# Power_Supply.net
KiCad netlist of a schematic drawn in EAGLE
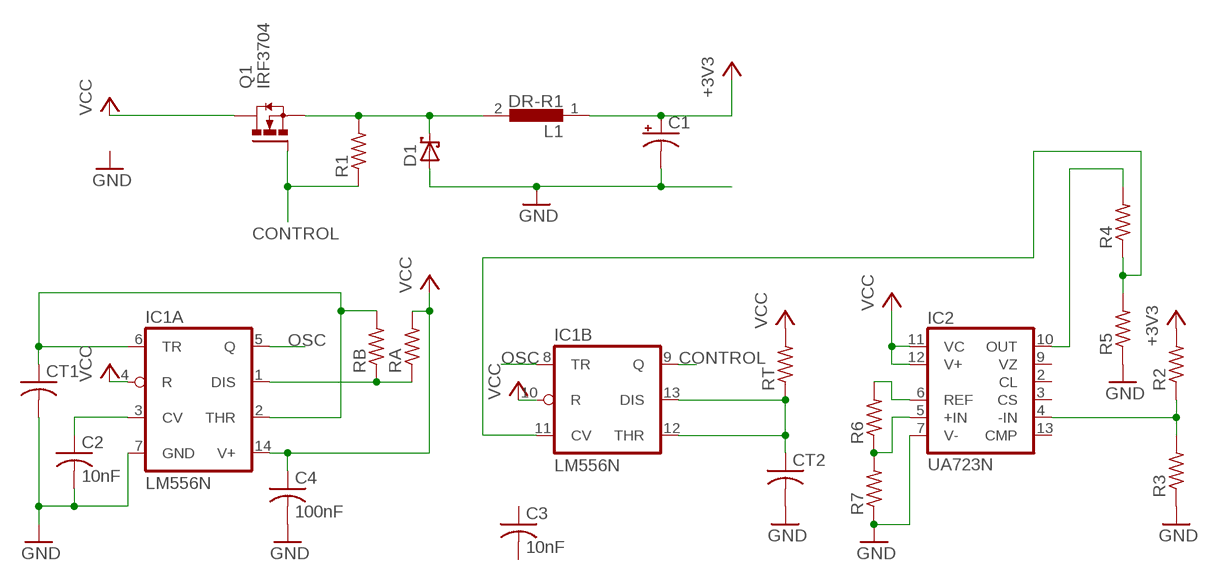
[diagram p0: schematic, sheet 1]

(export (version "E")
  (design (tool "Eeschema 10.0.6"))
  (components
    (comp (ref "C1")
      (value "CPOL-USE7.5-18")
      (footprint "eagle-import:E7,5-18")
      (libsource (lib "eagle-import") (part "CPOL-USE7.5-18"))
    )
    (comp (ref "C2")
      (value "10nF")
      (footprint "eagle-import:C050-025X075")
      (libsource (lib "eagle-import") (part "C-US050-025X075"))
    )
    (comp (ref "C3")
      (value "10nF")
      (footprint "eagle-import:C050-025X075")
      (libsource (lib "eagle-import") (part "C-US050-025X075"))
    )
    (comp (ref "C4")
      (value "100nF")
      (footprint "eagle-import:C050-025X075")
      (libsource (lib "eagle-import") (part "C-US050-025X075"))
    )
    (comp (ref "CT1")
      (value "C-US050-025X075")
      (footprint "eagle-import:C050-025X075")
      (libsource (lib "eagle-import") (part "C-US050-025X075"))
    )
    (comp (ref "CT2")
      (value "C-US050-025X075")
      (footprint "eagle-import:C050-025X075")
      (libsource (lib "eagle-import") (part "C-US050-025X075"))
    )
    (comp (ref "D1")
      (value "SCHOTTKY-DIODEC4111-15")
      (footprint "eagle-import:C4111-15")
      (libsource (lib "eagle-import") (part "SCHOTTKY-DIODEC4111-15"))
    )
    (comp (ref "IC1")
      (value "LM556N")
      (footprint "eagle-import:DIL14")
      (libsource (lib "eagle-import") (part "556NLM"))
    )
    (comp (ref "IC2")
      (value "UA723N")
      (footprint "eagle-import:DIL14")
      (libsource (lib "eagle-import") (part "723NUA"))
    )
    (comp (ref "L1")
      (value "DR-R1")
      (footprint "eagle-import:DR-R1")
      (libsource (lib "eagle-import") (part "DR-R1"))
    )
    (comp (ref "Q1")
      (value "IRF3704")
      (footprint "eagle-import:TO220AH")
      (libsource (lib "eagle-import") (part "IRF3704"))
    )
    (comp (ref "R1")
      (value "R-US_0207/10")
      (footprint "eagle-import:0207_10")
      (libsource (lib "eagle-import") (part "R-US_0207/10"))
    )
    (comp (ref "R2")
      (value "R-US_0207/10")
      (footprint "eagle-import:0207_10")
      (libsource (lib "eagle-import") (part "R-US_0207/10"))
    )
    (comp (ref "R3")
      (value "R-US_0207/10")
      (footprint "eagle-import:0207_10")
      (libsource (lib "eagle-import") (part "R-US_0207/10"))
    )
    (comp (ref "R4")
      (value "R-US_0207/10")
      (footprint "eagle-import:0207_10")
      (libsource (lib "eagle-import") (part "R-US_0207/10"))
    )
    (comp (ref "R5")
      (value "R-US_0207/10")
      (footprint "eagle-import:0207_10")
      (libsource (lib "eagle-import") (part "R-US_0207/10"))
    )
    (comp (ref "R6")
      (value "R-US_0207/10")
      (footprint "eagle-import:0207_10")
      (libsource (lib "eagle-import") (part "R-US_0207/10"))
    )
    (comp (ref "R7")
      (value "R-US_0207/10")
      (footprint "eagle-import:0207_10")
      (libsource (lib "eagle-import") (part "R-US_0207/10"))
    )
    (comp (ref "RA")
      (value "R-US_0207/10")
      (footprint "eagle-import:0207_10")
      (libsource (lib "eagle-import") (part "R-US_0207/10"))
    )
    (comp (ref "RB")
      (value "R-US_0207/10")
      (footprint "eagle-import:0207_10")
      (libsource (lib "eagle-import") (part "R-US_0207/10"))
    )
    (comp (ref "RT")
      (value "R-US_0207/10")
      (footprint "eagle-import:0207_10")
      (libsource (lib "eagle-import") (part "R-US_0207/10"))
    )
  )
  (nets
    (net (code "1") (name "+3V3") (class "Default")
      (node (ref "C1") (pin "+") (pinfunction "+_+") (pintype "passive"))
      (node (ref "L1") (pin "1") (pinfunction "1_1") (pintype "passive"))
      (node (ref "R2") (pin "2") (pinfunction "2_2") (pintype "passive"))
    )
    (net (code "2") (name "/CONTROL") (class "Default")
      (node (ref "IC1") (pin "9") (pinfunction "Q_9") (pintype "output"))
      (node (ref "Q1") (pin "B") (pinfunction "G_B") (pintype "passive"))
      (node (ref "R1") (pin "1") (pinfunction "1_1") (pintype "passive"))
    )
    (net (code "3") (name "/OSC") (class "Default")
      (node (ref "IC1") (pin "5") (pinfunction "Q_5") (pintype "output"))
      (node (ref "IC1") (pin "8") (pinfunction "TR_8") (pintype "input"))
    )
    (net (code "4") (name "GND") (class "Default")
      (node (ref "C1") (pin "-") (pinfunction "-_-") (pintype "passive"))
      (node (ref "C2") (pin "2") (pinfunction "2_2") (pintype "passive"))
      (node (ref "C4") (pin "2") (pinfunction "2_2") (pintype "passive"))
      (node (ref "CT1") (pin "2") (pinfunction "2_2") (pintype "passive"))
      (node (ref "CT2") (pin "2") (pinfunction "2_2") (pintype "passive"))
      (node (ref "D1") (pin "A") (pinfunction "A_A") (pintype "passive"))
      (node (ref "IC1") (pin "7") (pinfunction "GND_7") (pintype "power_in"))
      (node (ref "IC2") (pin "7") (pinfunction "V-_7") (pintype "input"))
      (node (ref "R3") (pin "1") (pinfunction "1_1") (pintype "passive"))
      (node (ref "R5") (pin "1") (pinfunction "1_1") (pintype "passive"))
      (node (ref "R7") (pin "1") (pinfunction "1_1") (pintype "passive"))
    )
    (net (code "5") (name "Net-(IC1A-CV)") (class "Default")
      (node (ref "C2") (pin "1") (pinfunction "1_1") (pintype "passive"))
      (node (ref "IC1") (pin "3") (pinfunction "CV_3") (pintype "input"))
    )
    (net (code "6") (name "Net-(IC1A-DIS)") (class "Default")
      (node (ref "IC1") (pin "1") (pinfunction "DIS_1") (pintype "input"))
      (node (ref "RA") (pin "1") (pinfunction "1_1") (pintype "passive"))
      (node (ref "RB") (pin "1") (pinfunction "1_1") (pintype "passive"))
    )
    (net (code "7") (name "Net-(IC1A-THR)") (class "Default")
      (node (ref "CT1") (pin "1") (pinfunction "1_1") (pintype "passive"))
      (node (ref "IC1") (pin "2") (pinfunction "THR_2") (pintype "input"))
      (node (ref "IC1") (pin "6") (pinfunction "TR_6") (pintype "input"))
      (node (ref "RB") (pin "2") (pinfunction "2_2") (pintype "passive"))
    )
    (net (code "8") (name "Net-(IC1B-CV)") (class "Default")
      (node (ref "IC1") (pin "11") (pinfunction "CV_11") (pintype "input"))
      (node (ref "R4") (pin "1") (pinfunction "1_1") (pintype "passive"))
      (node (ref "R5") (pin "2") (pinfunction "2_2") (pintype "passive"))
    )
    (net (code "9") (name "Net-(IC1B-DIS)") (class "Default")
      (node (ref "CT2") (pin "1") (pinfunction "1_1") (pintype "passive"))
      (node (ref "IC1") (pin "12") (pinfunction "THR_12") (pintype "input"))
      (node (ref "IC1") (pin "13") (pinfunction "DIS_13") (pintype "input"))
      (node (ref "RT") (pin "1") (pinfunction "1_1") (pintype "passive"))
    )
    (net (code "10") (name "Net-(IC2-+IN)") (class "Default")
      (node (ref "IC2") (pin "5") (pinfunction "+IN_5") (pintype "input"))
      (node (ref "R6") (pin "1") (pinfunction "1_1") (pintype "passive"))
      (node (ref "R7") (pin "2") (pinfunction "2_2") (pintype "passive"))
    )
    (net (code "11") (name "Net-(IC2--IN)") (class "Default")
      (node (ref "IC2") (pin "4") (pinfunction "-IN_4") (pintype "input"))
      (node (ref "R2") (pin "1") (pinfunction "1_1") (pintype "passive"))
      (node (ref "R3") (pin "2") (pinfunction "2_2") (pintype "passive"))
    )
    (net (code "12") (name "Net-(IC2-OUT)") (class "Default")
      (node (ref "IC2") (pin "10") (pinfunction "OUT_10") (pintype "output"))
      (node (ref "R4") (pin "2") (pinfunction "2_2") (pintype "passive"))
    )
    (net (code "13") (name "Net-(IC2-REF)") (class "Default")
      (node (ref "IC2") (pin "6") (pinfunction "REF_6") (pintype "output"))
      (node (ref "R6") (pin "2") (pinfunction "2_2") (pintype "passive"))
    )
    (net (code "14") (name "Net-(Q1-S)") (class "Default")
      (node (ref "D1") (pin "C") (pinfunction "C_C") (pintype "passive"))
      (node (ref "L1") (pin "2") (pinfunction "2_2") (pintype "passive"))
      (node (ref "Q1") (pin "E") (pinfunction "S_E") (pintype "passive"))
      (node (ref "R1") (pin "2") (pinfunction "2_2") (pintype "passive"))
    )
    (net (code "15") (name "VCC") (class "Default")
      (node (ref "C4") (pin "1") (pinfunction "1_1") (pintype "passive"))
      (node (ref "IC1") (pin "10") (pinfunction "R_10") (pintype "input"))
      (node (ref "IC1") (pin "14") (pinfunction "V+_14") (pintype "power_in"))
      (node (ref "IC1") (pin "4") (pinfunction "R_4") (pintype "input"))
      (node (ref "IC2") (pin "11") (pinfunction "VC_11") (pintype "input"))
      (node (ref "IC2") (pin "12") (pinfunction "V+_12") (pintype "input"))
      (node (ref "Q1") (pin "C") (pinfunction "D_C") (pintype "passive"))
      (node (ref "RA") (pin "2") (pinfunction "2_2") (pintype "passive"))
      (node (ref "RT") (pin "2") (pinfunction "2_2") (pintype "passive"))
    )
    (net (code "16") (name "unconnected-(C3-Pad1)") (class "Default")
      (node (ref "C3") (pin "1") (pinfunction "1_1") (pintype "passive"))
    )
    (net (code "17") (name "unconnected-(C3-Pad2)") (class "Default")
      (node (ref "C3") (pin "2") (pinfunction "2_2") (pintype "passive"))
    )
    (net (code "18") (name "unconnected-(IC2-CL-Pad2)") (class "Default")
      (node (ref "IC2") (pin "2") (pinfunction "CL_2") (pintype "input"))
    )
    (net (code "19") (name "unconnected-(IC2-CMP-Pad13)") (class "Default")
      (node (ref "IC2") (pin "13") (pinfunction "CMP_13") (pintype "passive"))
    )
    (net (code "20") (name "unconnected-(IC2-CS-Pad3)") (class "Default")
      (node (ref "IC2") (pin "3") (pinfunction "CS_3") (pintype "input"))
    )
    (net (code "21") (name "unconnected-(IC2-VZ-Pad9)") (class "Default")
      (node (ref "IC2") (pin "9") (pinfunction "VZ_9") (pintype "output"))
    )
  )
)
